# Interface_IO.net
KiCad netlist of a schematic drawn in Altium Designer
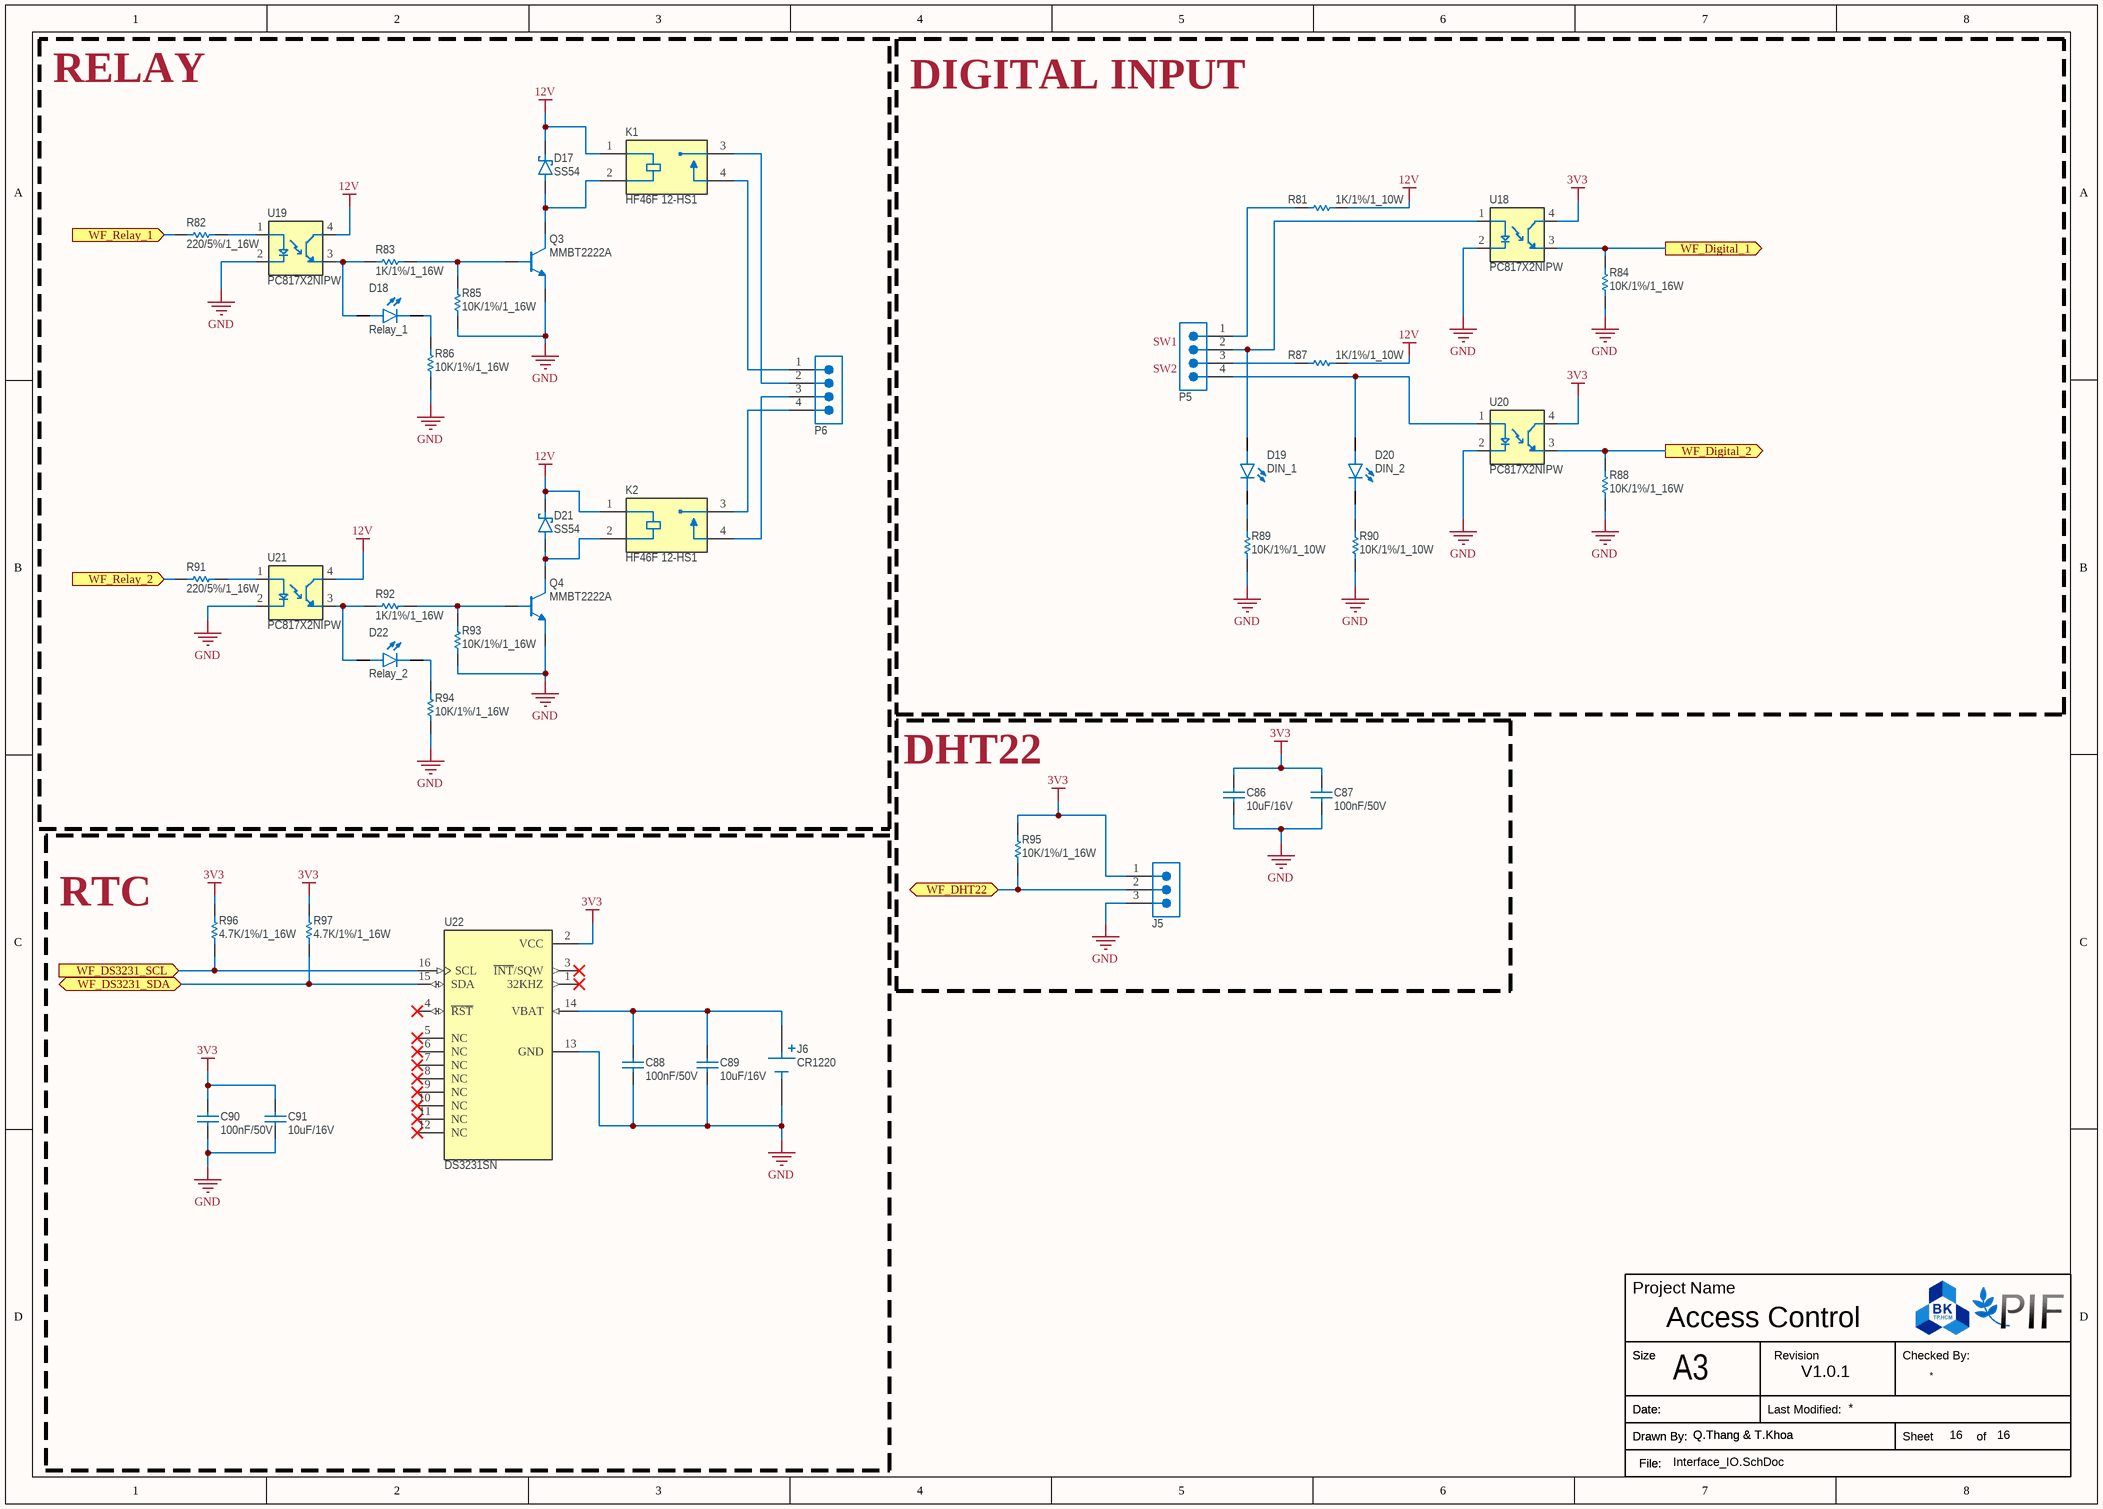
[diagram p0: Interface_IO.SchDoc]

(export (version "E")
  (design (tool "Eeschema 10.0.6"))
  (components
    (comp (ref "C86")
      (value "10uF/16V")
      (footprint "CAP_0603")
      (description "CAP, size 0603, 10uF, 16V")
      (fields (field (name "SUPPLY PART NUMBER") "Tụ Gốm 0603 10uF 16V"))
      (libsource (lib "BluetoothTracking") (part "Ceramic_Cap_10uF_16V_0603"))
    )
    (comp (ref "C87")
      (value "100nF/50V")
      (footprint "CAP_0603")
      (description "CAP, size 0603, 100nF, 50V")
      (fields (field (name "SUPPLY PART NUMBER") "Tụ Gốm 0603 100nF (0.1uF) 50V"))
      (libsource (lib "BluetoothTracking") (part "Ceramic_Cap_100nF_50V_0603"))
    )
    (comp (ref "C88")
      (value "100nF/50V")
      (footprint "CAP_0603")
      (description "CAP, size 0603, 100nF, 50V")
      (fields (field (name "SUPPLY PART NUMBER") "Tụ Gốm 0603 100nF (0.1uF) 50V"))
      (libsource (lib "BluetoothTracking") (part "Ceramic_Cap_100nF_50V_0603"))
    )
    (comp (ref "C89")
      (value "10uF/16V")
      (footprint "CAP_0603")
      (description "CAP, size 0603, 10uF, 16V")
      (fields (field (name "SUPPLY PART NUMBER") "Tụ Gốm 0603 10uF 16V"))
      (libsource (lib "BluetoothTracking") (part "Ceramic_Cap_10uF_16V_0603"))
    )
    (comp (ref "C90")
      (value "100nF/50V")
      (footprint "CAP_0603")
      (description "CAP, size 0603, 100nF, 50V")
      (fields (field (name "SUPPLY PART NUMBER") "Tụ Gốm 0603 100nF (0.1uF) 50V"))
      (libsource (lib "BluetoothTracking") (part "Ceramic_Cap_100nF_50V_0603"))
    )
    (comp (ref "C91")
      (value "10uF/16V")
      (footprint "CAP_0603")
      (description "CAP, size 0603, 10uF, 16V")
      (fields (field (name "SUPPLY PART NUMBER") "Tụ Gốm 0603 10uF 16V"))
      (libsource (lib "BluetoothTracking") (part "Ceramic_Cap_10uF_16V_0603"))
    )
    (comp (ref "D17")
      (value "SS54")
      (footprint "D_SMA")
      (description "Diode Schottky 40V 5A Surface Mount SMA")
      (fields (field (name "SUPPLY PART NUMBER") "SS54 SMA Diode Shotky 5A 40V"))
      (libsource (lib "BluetoothTracking") (part "Diode_SS54"))
    )
    (comp (ref "D18")
      (value "Relay_1")
      (footprint "LED_0603Y")
      (description "LED Yellow 0603")
      (fields (field (name "SUPPLY PART NUMBER") "LED Vàng 0603 Dán SMD Trong Suốt Harvatek"))
      (libsource (lib "BluetoothTracking") (part "LED_Yellow_0603"))
    )
    (comp (ref "D19")
      (value "DIN_1")
      (footprint "LED_0603Y")
      (description "LED Yellow 0603")
      (fields (field (name "SUPPLY PART NUMBER") "LED Vàng 0603 Dán SMD Trong Suốt Harvatek"))
      (libsource (lib "BluetoothTracking") (part "LED_Yellow_0603"))
    )
    (comp (ref "D20")
      (value "DIN_2")
      (footprint "LED_0603Y")
      (description "LED Yellow 0603")
      (fields (field (name "SUPPLY PART NUMBER") "LED Vàng 0603 Dán SMD Trong Suốt Harvatek"))
      (libsource (lib "BluetoothTracking") (part "LED_Yellow_0603"))
    )
    (comp (ref "D21")
      (value "SS54")
      (footprint "D_SMA")
      (description "Diode Schottky 40V 5A Surface Mount SMA")
      (fields (field (name "SUPPLY PART NUMBER") "SS54 SMA Diode Shotky 5A 40V"))
      (libsource (lib "BluetoothTracking") (part "Diode_SS54"))
    )
    (comp (ref "D22")
      (value "Relay_2")
      (footprint "LED_0603Y")
      (description "LED Yellow 0603")
      (fields (field (name "SUPPLY PART NUMBER") "LED Vàng 0603 Dán SMD Trong Suốt Harvatek"))
      (libsource (lib "BluetoothTracking") (part "LED_Yellow_0603"))
    )
    (comp (ref "J5")
      (value "3.81mm_3P")
      (footprint "Terminal_Block_3.81mm_3P")
      (description "Terminal Block THT, pitch 3.81mm, 3p, 300V 10A")
      (fields
        (field (name "SUPPLY PART NUMBER") "UL-3.81-3-R Terminal Block Plug-in Hàn PCB 3 Chân Cong 3.81mm 300V 10A ULO")
      )
      (libsource (lib "BluetoothTracking") (part "Terminal_Block_3.81mm_3P"))
    )
    (comp (ref "J6")
      (value "CR1220")
      (footprint "Battery_Holder_CR1220")
      (description "Coin Cell Battery Retainer, Horizontal SMT, for CR1220 Coin Cell Batteries, Tape & Reeled")
      (fields (field (name "SUPPLY PART NUMBER") "Đế Pin CR1220 Dán SMD"))
      (libsource (lib "BluetoothTracking") (part "Battery_Holder_CR1220"))
    )
    (comp (ref "K1")
      (value "HF46F 12-HS1")
      (footprint "RELAY_HF46F_005-HS1")
      (description "4 chân xuyên lỗ")
      (fields (field (name "SUPPLY PART NUMBER") "HF46F 12-HS1 Rơ Le 12VDC 5A SPST-NO 4 Chân"))
      (libsource (lib "BluetoothTracking") (part "HF46F 12-HS1"))
    )
    (comp (ref "K2")
      (value "HF46F 12-HS1")
      (footprint "RELAY_HF46F_005-HS1")
      (description "4 chân xuyên lỗ")
      (fields (field (name "SUPPLY PART NUMBER") "HF46F 12-HS1 Rơ Le 12VDC 5A SPST-NO 4 Chân"))
      (libsource (lib "BluetoothTracking") (part "HF46F 12-HS1"))
    )
    (comp (ref "P5")
      (value "3.81mm_4P")
      (footprint "Terminal_Block_3.81mm_4P")
      (description "Terminal Block THT, pitch 3.81mm, 4p, 300V 10A")
      (fields
        (field (name "SUPPLY PART NUMBER") "UL-3.81-4-R Terminal Block Plug-in Hàn PCB 4 Chân Cong 3.81mm 300V 10A ULO")
      )
      (libsource (lib "BluetoothTracking") (part "Terminal_Block_3.81mm_4P"))
    )
    (comp (ref "P6")
      (value "3.81mm_4P")
      (footprint "Terminal_Block_3.81mm_4P")
      (description "Terminal Block THT, pitch 3.81mm, 4p, 300V 10A")
      (fields
        (field (name "SUPPLY PART NUMBER") "UL-3.81-4-R Terminal Block Plug-in Hàn PCB 4 Chân Cong 3.81mm 300V 10A ULO")
      )
      (libsource (lib "BluetoothTracking") (part "Terminal_Block_3.81mm_4P"))
    )
    (comp (ref "Q3")
      (value "MMBT2222A")
      (footprint "SOT-23")
      (description "Điện áp Vce max: 40V, dòng Ic max: 0.6A, công suất: 0.3W")
      (fields (field (name "SUPPLY PART NUMBER") "MMBT2222A 1P Transistor NPN 40V 0.6A 3 Chân SOT-23"))
      (libsource (lib "BluetoothTracking") (part "MMBT2222A"))
    )
    (comp (ref "Q4")
      (value "MMBT2222A")
      (footprint "SOT-23")
      (description "Điện áp Vce max: 40V, dòng Ic max: 0.6A, công suất: 0.3W")
      (fields (field (name "SUPPLY PART NUMBER") "MMBT2222A 1P Transistor NPN 40V 0.6A 3 Chân SOT-23"))
      (libsource (lib "BluetoothTracking") (part "MMBT2222A"))
    )
    (comp (ref "R81")
      (value "1K/1%/1_10W")
      (footprint "Resistor_0603")
      (description "Resistor 0603 1KOhm 1% 1_10W")
      (fields (field (name "SUPPLY PART NUMBER") "Điện Trở 1 KOhm 0603 1%"))
      (libsource (lib "BluetoothTracking") (part "Res_1K_0603_1%"))
    )
    (comp (ref "R82")
      (value "220/5%/1_16W")
      (footprint "RESISTOR_0402")
      (description "Resistor 0402 220 Ohm 5% 1_16W")
      (fields (field (name "SUPPLY PART NUMBER") "Điện Trở 220 Ohm 0402 5%"))
      (libsource (lib "BluetoothTracking") (part "Res_220R_0402_5%"))
    )
    (comp (ref "R83")
      (value "1K/1%/1_16W")
      (footprint "RESISTOR_0402")
      (description "Resistor 0402 1KOhm 1% 1_16W")
      (fields (field (name "SUPPLY PART NUMBER") "Điện Trở 1 KOhm 0402 1%"))
      (libsource (lib "BluetoothTracking") (part "Res_1K_0402_1%"))
    )
    (comp (ref "R84")
      (value "10K/1%/1_16W")
      (footprint "RESISTOR_0402")
      (description "Resistor 0402 10KOhm 1% 1_16W")
      (fields (field (name "SUPPLY PART NUMBER") "Điện Trở 10 KOhm 0402 1%"))
      (libsource (lib "BluetoothTracking") (part "Res_10K_0402_1%"))
    )
    (comp (ref "R85")
      (value "10K/1%/1_16W")
      (footprint "RESISTOR_0402")
      (description "Resistor 0402 10KOhm 1% 1_16W")
      (fields (field (name "SUPPLY PART NUMBER") "Điện Trở 10 KOhm 0402 1%"))
      (libsource (lib "BluetoothTracking") (part "Res_10K_0402_1%"))
    )
    (comp (ref "R86")
      (value "10K/1%/1_16W")
      (footprint "RESISTOR_0402")
      (description "Resistor 0402 10KOhm 1% 1_16W")
      (fields (field (name "SUPPLY PART NUMBER") "Điện Trở 10 KOhm 0402 1%"))
      (libsource (lib "BluetoothTracking") (part "Res_10K_0402_1%"))
    )
    (comp (ref "R87")
      (value "1K/1%/1_10W")
      (footprint "Resistor_0603")
      (description "Resistor 0603 1KOhm 1% 1_10W")
      (fields (field (name "SUPPLY PART NUMBER") "Điện Trở 1 KOhm 0603 1%"))
      (libsource (lib "BluetoothTracking") (part "Res_1K_0603_1%"))
    )
    (comp (ref "R88")
      (value "10K/1%/1_16W")
      (footprint "RESISTOR_0402")
      (description "Resistor 0402 10KOhm 1% 1_16W")
      (fields (field (name "SUPPLY PART NUMBER") "Điện Trở 10 KOhm 0402 1%"))
      (libsource (lib "BluetoothTracking") (part "Res_10K_0402_1%"))
    )
    (comp (ref "R89")
      (value "10K/1%/1_10W")
      (footprint "Resistor_0603")
      (description "Resistor 0603 10KOhm 1% 1_10W")
      (fields (field (name "SUPPLY PART NUMBER") "Điện Trở 10 KOhm 0603 1%"))
      (libsource (lib "BluetoothTracking") (part "Res_10K_0603_1%"))
    )
    (comp (ref "R90")
      (value "10K/1%/1_10W")
      (footprint "Resistor_0603")
      (description "Resistor 0603 10KOhm 1% 1_10W")
      (fields (field (name "SUPPLY PART NUMBER") "Điện Trở 10 KOhm 0603 1%"))
      (libsource (lib "BluetoothTracking") (part "Res_10K_0603_1%"))
    )
    (comp (ref "R91")
      (value "220/5%/1_16W")
      (footprint "RESISTOR_0402")
      (description "Resistor 0402 220 Ohm 5% 1_16W")
      (fields (field (name "SUPPLY PART NUMBER") "Điện Trở 220 Ohm 0402 5%"))
      (libsource (lib "BluetoothTracking") (part "Res_220R_0402_5%"))
    )
    (comp (ref "R92")
      (value "1K/1%/1_16W")
      (footprint "RESISTOR_0402")
      (description "Resistor 0402 1KOhm 1% 1_16W")
      (fields (field (name "SUPPLY PART NUMBER") "Điện Trở 1 KOhm 0402 1%"))
      (libsource (lib "BluetoothTracking") (part "Res_1K_0402_1%"))
    )
    (comp (ref "R93")
      (value "10K/1%/1_16W")
      (footprint "RESISTOR_0402")
      (description "Resistor 0402 10KOhm 1% 1_16W")
      (fields (field (name "SUPPLY PART NUMBER") "Điện Trở 10 KOhm 0402 1%"))
      (libsource (lib "BluetoothTracking") (part "Res_10K_0402_1%"))
    )
    (comp (ref "R94")
      (value "10K/1%/1_16W")
      (footprint "RESISTOR_0402")
      (description "Resistor 0402 10KOhm 1% 1_16W")
      (fields (field (name "SUPPLY PART NUMBER") "Điện Trở 10 KOhm 0402 1%"))
      (libsource (lib "BluetoothTracking") (part "Res_10K_0402_1%"))
    )
    (comp (ref "R95")
      (value "10K/1%/1_16W")
      (footprint "RESISTOR_0402")
      (description "Resistor 0402 10KOhm 1% 1_16W")
      (fields (field (name "SUPPLY PART NUMBER") "Điện Trở 10 KOhm 0402 1%"))
      (libsource (lib "BluetoothTracking") (part "Res_10K_0402_1%"))
    )
    (comp (ref "R96")
      (value "4.7K/1%/1_16W")
      (footprint "RESISTOR_0402")
      (description "Resistor 0402 4.7KOhm 1% 1_16W")
      (fields (field (name "SUPPLY PART NUMBER") "Điện Trở 4.7 KOhm 0402 1%"))
      (libsource (lib "BluetoothTracking") (part "Res_4.7K_0402_1%"))
    )
    (comp (ref "R97")
      (value "4.7K/1%/1_16W")
      (footprint "RESISTOR_0402")
      (description "Resistor 0402 4.7KOhm 1% 1_16W")
      (fields (field (name "SUPPLY PART NUMBER") "Điện Trở 4.7 KOhm 0402 1%"))
      (libsource (lib "BluetoothTracking") (part "Res_4.7K_0402_1%"))
    )
    (comp (ref "U18")
      (value "PC817X2NIPW")
      (footprint "SOP-4")
      (description "Optocoupler DC-IN 1-CH Transistor DC-OUT 4-Pin")
      (fields
        (field (name "SUPPLY PART NUMBER") "PC817X2NIPW Optoisolator Transistor Output 5000Vrms 1 Channel, SOP-4")
      )
      (libsource (lib "BluetoothTracking") (part "PC817X2NIPW"))
    )
    (comp (ref "U19")
      (value "PC817X2NIPW")
      (footprint "SOP-4")
      (description "Optocoupler DC-IN 1-CH Transistor DC-OUT 4-Pin")
      (fields
        (field (name "SUPPLY PART NUMBER") "PC817X2NIPW Optoisolator Transistor Output 5000Vrms 1 Channel, SOP-4")
      )
      (libsource (lib "BluetoothTracking") (part "PC817X2NIPW"))
    )
    (comp (ref "U20")
      (value "PC817X2NIPW")
      (footprint "SOP-4")
      (description "Optocoupler DC-IN 1-CH Transistor DC-OUT 4-Pin")
      (fields
        (field (name "SUPPLY PART NUMBER") "PC817X2NIPW Optoisolator Transistor Output 5000Vrms 1 Channel, SOP-4")
      )
      (libsource (lib "BluetoothTracking") (part "PC817X2NIPW"))
    )
    (comp (ref "U21")
      (value "PC817X2NIPW")
      (footprint "SOP-4")
      (description "Optocoupler DC-IN 1-CH Transistor DC-OUT 4-Pin")
      (fields
        (field (name "SUPPLY PART NUMBER") "PC817X2NIPW Optoisolator Transistor Output 5000Vrms 1 Channel, SOP-4")
      )
      (libsource (lib "BluetoothTracking") (part "PC817X2NIPW"))
    )
    (comp (ref "U22")
      (value "DS3231SN")
      (footprint "SOIC-16")
      (description "Real Time Clock (RTC) IC Clock/Calendar - I²C, 2-Wire Serial 16-SOIC (0.295, 7.50mm Width)")
      (fields (field (name "SUPPLY PART NUMBER") "DS3231SN#T&R IC RTC Clock/Calendar"))
      (libsource (lib "BluetoothTracking") (part "DS3231SN"))
    )
  )
  (nets
    (net (code "1") (name "/WF_DHT22") (class "Default")
      (node (ref "J5") (pin "2") (pinfunction "2_2") (pintype "passive"))
      (node (ref "R95") (pin "1") (pinfunction "1_1") (pintype "passive"))
    )
    (net (code "2") (name "/WF_DS3231_SCL") (class "Default")
      (node (ref "R96") (pin "1") (pinfunction "1_1") (pintype "passive"))
      (node (ref "U22") (pin "16") (pinfunction "SCL_16") (pintype "input"))
    )
    (net (code "3") (name "/WF_DS3231_SDA") (class "Default")
      (node (ref "R97") (pin "1") (pinfunction "1_1") (pintype "passive"))
      (node (ref "U22") (pin "15") (pinfunction "SDA_15") (pintype "bidirectional"))
    )
    (net (code "4") (name "/WF_Digital_1") (class "Default")
      (node (ref "R84") (pin "2") (pinfunction "2_2") (pintype "passive"))
      (node (ref "U18") (pin "3") (pinfunction "ET_3") (pintype "passive"))
    )
    (net (code "5") (name "/WF_Digital_2") (class "Default")
      (node (ref "R88") (pin "2") (pinfunction "2_2") (pintype "passive"))
      (node (ref "U20") (pin "3") (pinfunction "ET_3") (pintype "passive"))
    )
    (net (code "6") (name "/WF_Relay_1") (class "Default")
      (node (ref "R82") (pin "1") (pinfunction "1_1") (pintype "passive"))
    )
    (net (code "7") (name "/WF_Relay_2") (class "Default")
      (node (ref "R91") (pin "1") (pinfunction "1_1") (pintype "passive"))
    )
    (net (code "8") (name "3V3") (class "Default")
      (node (ref "C86") (pin "2") (pinfunction "2_2") (pintype "passive"))
      (node (ref "C87") (pin "2") (pinfunction "2_2") (pintype "passive"))
      (node (ref "C90") (pin "2") (pinfunction "2_2") (pintype "passive"))
      (node (ref "C91") (pin "2") (pinfunction "2_2") (pintype "passive"))
      (node (ref "J5") (pin "1") (pinfunction "1_1") (pintype "passive"))
      (node (ref "R95") (pin "2") (pinfunction "2_2") (pintype "passive"))
      (node (ref "R96") (pin "2") (pinfunction "2_2") (pintype "passive"))
      (node (ref "R97") (pin "2") (pinfunction "2_2") (pintype "passive"))
      (node (ref "U18") (pin "4") (pinfunction "CT_4") (pintype "passive"))
      (node (ref "U20") (pin "4") (pinfunction "CT_4") (pintype "passive"))
      (node (ref "U22") (pin "2") (pinfunction "VCC_2") (pintype "power_in"))
    )
    (net (code "9") (name "12V") (class "Default")
      (node (ref "D17") (pin "1") (pinfunction "C_1") (pintype "passive"))
      (node (ref "D21") (pin "1") (pinfunction "C_1") (pintype "passive"))
      (node (ref "K1") (pin "1") (pinfunction "COIL1_1") (pintype "passive"))
      (node (ref "K2") (pin "1") (pinfunction "COIL1_1") (pintype "passive"))
      (node (ref "R81") (pin "1") (pinfunction "1_1") (pintype "passive"))
      (node (ref "R87") (pin "1") (pinfunction "1_1") (pintype "passive"))
      (node (ref "U19") (pin "4") (pinfunction "CT_4") (pintype "passive"))
      (node (ref "U21") (pin "4") (pinfunction "CT_4") (pintype "passive"))
    )
    (net (code "10") (name "GND") (class "Default")
      (node (ref "C86") (pin "1") (pinfunction "1_1") (pintype "passive"))
      (node (ref "C87") (pin "1") (pinfunction "1_1") (pintype "passive"))
      (node (ref "C88") (pin "1") (pinfunction "1_1") (pintype "passive"))
      (node (ref "C89") (pin "1") (pinfunction "1_1") (pintype "passive"))
      (node (ref "C90") (pin "1") (pinfunction "1_1") (pintype "passive"))
      (node (ref "C91") (pin "1") (pinfunction "1_1") (pintype "passive"))
      (node (ref "J5") (pin "3") (pinfunction "3_3") (pintype "passive"))
      (node (ref "J6") (pin "N") (pinfunction "NEG_N") (pintype "passive"))
      (node (ref "Q3") (pin "2") (pinfunction "E_2") (pintype "passive"))
      (node (ref "Q4") (pin "2") (pinfunction "E_2") (pintype "passive"))
      (node (ref "R84") (pin "1") (pinfunction "1_1") (pintype "passive"))
      (node (ref "R85") (pin "1") (pinfunction "1_1") (pintype "passive"))
      (node (ref "R86") (pin "1") (pinfunction "1_1") (pintype "passive"))
      (node (ref "R88") (pin "1") (pinfunction "1_1") (pintype "passive"))
      (node (ref "R89") (pin "1") (pinfunction "1_1") (pintype "passive"))
      (node (ref "R90") (pin "1") (pinfunction "1_1") (pintype "passive"))
      (node (ref "R93") (pin "1") (pinfunction "1_1") (pintype "passive"))
      (node (ref "R94") (pin "1") (pinfunction "1_1") (pintype "passive"))
      (node (ref "U18") (pin "2") (pinfunction "C_2") (pintype "passive"))
      (node (ref "U19") (pin "2") (pinfunction "C_2") (pintype "passive"))
      (node (ref "U20") (pin "2") (pinfunction "C_2") (pintype "passive"))
      (node (ref "U21") (pin "2") (pinfunction "C_2") (pintype "passive"))
      (node (ref "U22") (pin "13") (pinfunction "GND_13") (pintype "power_in"))
    )
    (net (code "11") (name "Net-(D17-A)") (class "Default")
      (node (ref "D17") (pin "2") (pinfunction "A_2") (pintype "passive"))
      (node (ref "K1") (pin "2") (pinfunction "COIL2_2") (pintype "passive"))
      (node (ref "Q3") (pin "3") (pinfunction "C_3") (pintype "passive"))
    )
    (net (code "12") (name "Net-(D18-PadC)") (class "Default")
      (node (ref "D18") (pin "C") (pinfunction "C_C") (pintype "passive"))
      (node (ref "R86") (pin "2") (pinfunction "2_2") (pintype "passive"))
    )
    (net (code "13") (name "Net-(D19-PadC)") (class "Default")
      (node (ref "D19") (pin "C") (pinfunction "C_C") (pintype "passive"))
      (node (ref "R89") (pin "2") (pinfunction "2_2") (pintype "passive"))
    )
    (net (code "14") (name "Net-(D20-PadC)") (class "Default")
      (node (ref "D20") (pin "C") (pinfunction "C_C") (pintype "passive"))
      (node (ref "R90") (pin "2") (pinfunction "2_2") (pintype "passive"))
    )
    (net (code "15") (name "Net-(D21-A)") (class "Default")
      (node (ref "D21") (pin "2") (pinfunction "A_2") (pintype "passive"))
      (node (ref "K2") (pin "2") (pinfunction "COIL2_2") (pintype "passive"))
      (node (ref "Q4") (pin "3") (pinfunction "C_3") (pintype "passive"))
    )
    (net (code "16") (name "Net-(D22-PadC)") (class "Default")
      (node (ref "D22") (pin "C") (pinfunction "C_C") (pintype "passive"))
      (node (ref "R94") (pin "2") (pinfunction "2_2") (pintype "passive"))
    )
    (net (code "17") (name "Net-(J6-POS)") (class "Default")
      (node (ref "C88") (pin "2") (pinfunction "2_2") (pintype "passive"))
      (node (ref "C89") (pin "2") (pinfunction "2_2") (pintype "passive"))
      (node (ref "J6") (pin "P") (pinfunction "POS_P") (pintype "passive"))
      (node (ref "U22") (pin "14") (pinfunction "VBAT_14") (pintype "input"))
    )
    (net (code "18") (name "Net-(K1-COM)") (class "Default")
      (node (ref "K1") (pin "3") (pinfunction "COM_3") (pintype "passive"))
      (node (ref "P6") (pin "2") (pinfunction "2_2") (pintype "passive"))
    )
    (net (code "19") (name "Net-(K1-NO)") (class "Default")
      (node (ref "K1") (pin "4") (pinfunction "NO_4") (pintype "passive"))
      (node (ref "P6") (pin "1") (pinfunction "1_1") (pintype "passive"))
    )
    (net (code "20") (name "Net-(K2-COM)") (class "Default")
      (node (ref "K2") (pin "3") (pinfunction "COM_3") (pintype "passive"))
      (node (ref "P6") (pin "4") (pinfunction "4_4") (pintype "passive"))
    )
    (net (code "21") (name "Net-(K2-NO)") (class "Default")
      (node (ref "K2") (pin "4") (pinfunction "NO_4") (pintype "passive"))
      (node (ref "P6") (pin "3") (pinfunction "3_3") (pintype "passive"))
    )
    (net (code "22") (name "Net-(P5-Pad1)") (class "Default")
      (node (ref "P5") (pin "1") (pinfunction "1_1") (pintype "passive"))
      (node (ref "R81") (pin "2") (pinfunction "2_2") (pintype "passive"))
    )
    (net (code "23") (name "Net-(P5-Pad3)") (class "Default")
      (node (ref "P5") (pin "3") (pinfunction "3_3") (pintype "passive"))
      (node (ref "R87") (pin "2") (pinfunction "2_2") (pintype "passive"))
    )
    (net (code "24") (name "Net-(Q3-B)") (class "Default")
      (node (ref "Q3") (pin "1") (pinfunction "B_1") (pintype "passive"))
      (node (ref "R83") (pin "2") (pinfunction "2_2") (pintype "passive"))
      (node (ref "R85") (pin "2") (pinfunction "2_2") (pintype "passive"))
    )
    (net (code "25") (name "Net-(Q4-B)") (class "Default")
      (node (ref "Q4") (pin "1") (pinfunction "B_1") (pintype "passive"))
      (node (ref "R92") (pin "2") (pinfunction "2_2") (pintype "passive"))
      (node (ref "R93") (pin "2") (pinfunction "2_2") (pintype "passive"))
    )
    (net (code "26") (name "Net-(U18-A)") (class "Default")
      (node (ref "D19") (pin "A") (pinfunction "A_A") (pintype "passive"))
      (node (ref "P5") (pin "2") (pinfunction "2_2") (pintype "passive"))
      (node (ref "U18") (pin "1") (pinfunction "A_1") (pintype "passive"))
    )
    (net (code "27") (name "Net-(U19-A)") (class "Default")
      (node (ref "R82") (pin "2") (pinfunction "2_2") (pintype "passive"))
      (node (ref "U19") (pin "1") (pinfunction "A_1") (pintype "passive"))
    )
    (net (code "28") (name "Net-(U19-ET)") (class "Default")
      (node (ref "D18") (pin "A") (pinfunction "A_A") (pintype "passive"))
      (node (ref "R83") (pin "1") (pinfunction "1_1") (pintype "passive"))
      (node (ref "U19") (pin "3") (pinfunction "ET_3") (pintype "passive"))
    )
    (net (code "29") (name "Net-(U20-A)") (class "Default")
      (node (ref "D20") (pin "A") (pinfunction "A_A") (pintype "passive"))
      (node (ref "P5") (pin "4") (pinfunction "4_4") (pintype "passive"))
      (node (ref "U20") (pin "1") (pinfunction "A_1") (pintype "passive"))
    )
    (net (code "30") (name "Net-(U21-A)") (class "Default")
      (node (ref "R91") (pin "2") (pinfunction "2_2") (pintype "passive"))
      (node (ref "U21") (pin "1") (pinfunction "A_1") (pintype "passive"))
    )
    (net (code "31") (name "Net-(U21-ET)") (class "Default")
      (node (ref "D22") (pin "A") (pinfunction "A_A") (pintype "passive"))
      (node (ref "R92") (pin "1") (pinfunction "1_1") (pintype "passive"))
      (node (ref "U21") (pin "3") (pinfunction "ET_3") (pintype "passive"))
    )
    (net (code "32") (name "unconnected-(U22-32KHZ-Pad1)") (class "Default")
      (node (ref "U22") (pin "1") (pinfunction "32KHZ_1") (pintype "output+no_connect"))
    )
    (net (code "33") (name "unconnected-(U22-NC-Pad5)") (class "Default")
      (node (ref "U22") (pin "5") (pinfunction "NC_5") (pintype "passive+no_connect"))
    )
    (net (code "34") (name "unconnected-(U22-NC-Pad6)") (class "Default")
      (node (ref "U22") (pin "6") (pinfunction "NC_6") (pintype "passive+no_connect"))
    )
    (net (code "35") (name "unconnected-(U22-NC-Pad7)") (class "Default")
      (node (ref "U22") (pin "7") (pinfunction "NC_7") (pintype "passive+no_connect"))
    )
    (net (code "36") (name "unconnected-(U22-NC-Pad8)") (class "Default")
      (node (ref "U22") (pin "8") (pinfunction "NC_8") (pintype "passive+no_connect"))
    )
    (net (code "37") (name "unconnected-(U22-NC-Pad9)") (class "Default")
      (node (ref "U22") (pin "9") (pinfunction "NC_9") (pintype "passive+no_connect"))
    )
    (net (code "38") (name "unconnected-(U22-NC-Pad10)") (class "Default")
      (node (ref "U22") (pin "10") (pinfunction "NC_10") (pintype "passive+no_connect"))
    )
    (net (code "39") (name "unconnected-(U22-NC-Pad11)") (class "Default")
      (node (ref "U22") (pin "11") (pinfunction "NC_11") (pintype "passive+no_connect"))
    )
    (net (code "40") (name "unconnected-(U22-NC-Pad12)") (class "Default")
      (node (ref "U22") (pin "12") (pinfunction "NC_12") (pintype "passive+no_connect"))
    )
    (net (code "41") (name "unconnected-(U22-~{INT}{slash}SQW-Pad3)") (class "Default")
      (node (ref "U22") (pin "3") (pinfunction "~{INT}/SQW_3") (pintype "output+no_connect"))
    )
    (net (code "42") (name "unconnected-(U22-~{RST}-Pad4)") (class "Default")
      (node (ref "U22") (pin "4") (pinfunction "~{RST}_4") (pintype "bidirectional+no_connect"))
    )
  )
)
